# IDCI_WifiNode_CPU1.net
KiCad netlist of a schematic drawn in Altium Designer
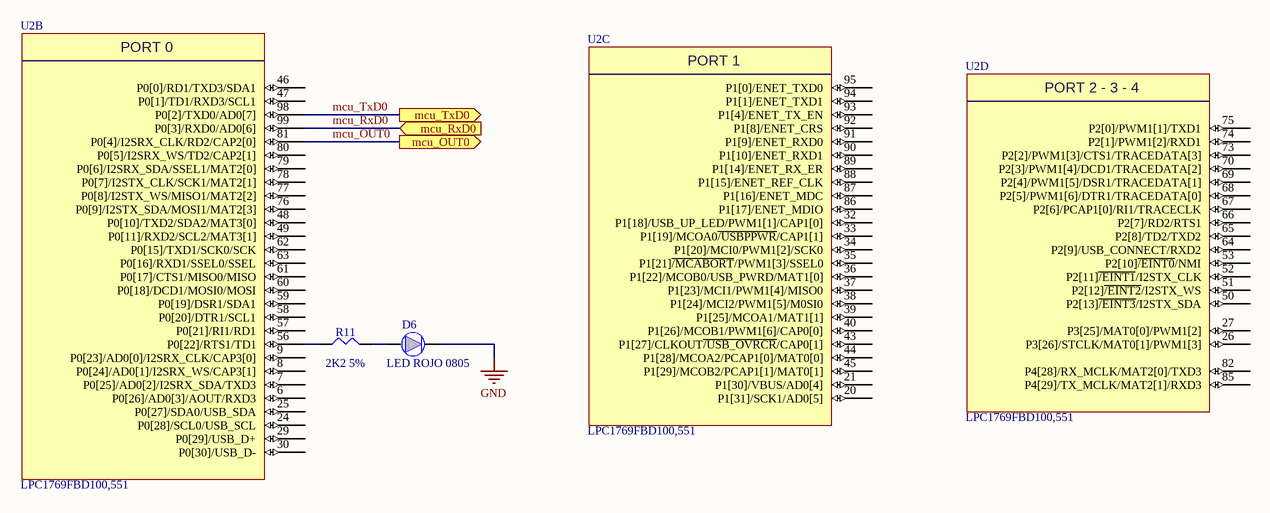
[diagram p0: IDCI_WifiNode_CPU1.SchDoc]

(export (version "E")
  (design (tool "Eeschema 10.0.6"))
  (components
    (comp (ref "D6")
      (value "LED ROJO 0805")
      (footprint "LED_0805")
      (libsource (lib "IDCI_WifiNode_2_R00") (part "LED_DIODE"))
    )
    (comp (ref "R11")
      (value "2K2 5%")
      (footprint "R_0805")
      (libsource (lib "IDCI_WifiNode_2_R00") (part "Resistor"))
    )
    (comp (ref "U2")
      (value "LPC1769FBD100,551")
      (footprint "LQFP_100")
      (description "Mcu Cortex M3 LQFP100")
      (libsource (lib "IDCI_WifiNode_2_R00") (part "LPC1769FBD100_Multipart"))
    )
  )
  (nets
    (net (code "1") (name "/mcu_OUT0") (class "Default")
      (node (ref "U2") (pin "81") (pinfunction "P0[4]/I2SRX_CLK/RD2/CAP2[0]_81") (pintype "bidirectional"))
    )
    (net (code "2") (name "/mcu_RxD0") (class "Default")
      (node (ref "U2") (pin "99") (pinfunction "P0[3]/RXD0/AD0[6]_99") (pintype "bidirectional"))
    )
    (net (code "3") (name "/mcu_TxD0") (class "Default")
      (node (ref "U2") (pin "98") (pinfunction "P0[2]/TXD0/AD0[7]_98") (pintype "bidirectional"))
    )
    (net (code "4") (name "GND") (class "Default")
      (node (ref "D6") (pin "2") (pinfunction "2_2") (pintype "passive"))
    )
    (net (code "5") (name "Net-(D6-Pad1)") (class "Default")
      (node (ref "D6") (pin "1") (pinfunction "1_1") (pintype "passive"))
      (node (ref "R11") (pin "2") (pinfunction "2_2") (pintype "passive"))
    )
    (net (code "6") (name "Net-(U2B-P0[22]{slash}RTS1{slash}TD1)") (class "Default")
      (node (ref "R11") (pin "1") (pinfunction "1_1") (pintype "passive"))
      (node (ref "U2") (pin "56") (pinfunction "P0[22]/RTS1/TD1_56") (pintype "bidirectional"))
    )
    (net (code "7") (name "unconnected-(U2B-P0[0]{slash}RD1{slash}TXD3{slash}SDA1-Pad46)") (class "Default")
      (node (ref "U2") (pin "46") (pinfunction "P0[0]/RD1/TXD3/SDA1_46") (pintype "bidirectional"))
    )
    (net (code "8") (name "unconnected-(U2B-P0[1]{slash}TD1{slash}RXD3{slash}SCL1-Pad47)") (class "Default")
      (node (ref "U2") (pin "47") (pinfunction "P0[1]/TD1/RXD3/SCL1_47") (pintype "bidirectional"))
    )
    (net (code "9") (name "unconnected-(U2B-P0[5]{slash}I2SRX_WS{slash}TD2{slash}CAP2[1]-Pad80)") (class "Default")
      (node (ref "U2") (pin "80") (pinfunction "P0[5]/I2SRX_WS/TD2/CAP2[1]_80") (pintype "bidirectional"))
    )
    (net (code "10") (name "unconnected-(U2B-P0[6]{slash}I2SRX_SDA{slash}SSEL1{slash}MAT2[0]-Pad79)") (class "Default")
      (node (ref "U2") (pin "79") (pinfunction "P0[6]/I2SRX_SDA/SSEL1/MAT2[0]_79") (pintype "bidirectional"))
    )
    (net (code "11") (name "unconnected-(U2B-P0[7]{slash}I2STX_CLK{slash}SCK1{slash}MAT2[1]-Pad78)") (class "Default")
      (node (ref "U2") (pin "78") (pinfunction "P0[7]/I2STX_CLK/SCK1/MAT2[1]_78") (pintype "bidirectional"))
    )
    (net (code "12") (name "unconnected-(U2B-P0[8]{slash}I2STX_WS{slash}MISO1{slash}MAT2[2]-Pad77)") (class "Default")
      (node (ref "U2") (pin "77") (pinfunction "P0[8]/I2STX_WS/MISO1/MAT2[2]_77") (pintype "bidirectional"))
    )
    (net (code "13") (name "unconnected-(U2B-P0[9]{slash}I2STX_SDA{slash}MOSI1{slash}MAT2[3]-Pad76)") (class "Default")
      (node (ref "U2") (pin "76") (pinfunction "P0[9]/I2STX_SDA/MOSI1/MAT2[3]_76") (pintype "bidirectional"))
    )
    (net (code "14") (name "unconnected-(U2B-P0[10]{slash}TXD2{slash}SDA2{slash}MAT3[0]-Pad48)") (class "Default")
      (node (ref "U2") (pin "48") (pinfunction "P0[10]/TXD2/SDA2/MAT3[0]_48") (pintype "bidirectional"))
    )
    (net (code "15") (name "unconnected-(U2B-P0[11]{slash}RXD2{slash}SCL2{slash}MAT3[1]-Pad49)") (class "Default")
      (node (ref "U2") (pin "49") (pinfunction "P0[11]/RXD2/SCL2/MAT3[1]_49") (pintype "bidirectional"))
    )
    (net (code "16") (name "unconnected-(U2B-P0[15]{slash}TXD1{slash}SCK0{slash}SCK-Pad62)") (class "Default")
      (node (ref "U2") (pin "62") (pinfunction "P0[15]/TXD1/SCK0/SCK_62") (pintype "bidirectional"))
    )
    (net (code "17") (name "unconnected-(U2B-P0[16]{slash}RXD1{slash}SSEL0{slash}SSEL-Pad63)") (class "Default")
      (node (ref "U2") (pin "63") (pinfunction "P0[16]/RXD1/SSEL0/SSEL_63") (pintype "bidirectional"))
    )
    (net (code "18") (name "unconnected-(U2B-P0[17]{slash}CTS1{slash}MISO0{slash}MISO-Pad61)") (class "Default")
      (node (ref "U2") (pin "61") (pinfunction "P0[17]/CTS1/MISO0/MISO_61") (pintype "bidirectional"))
    )
    (net (code "19") (name "unconnected-(U2B-P0[18]{slash}DCD1{slash}MOSI0{slash}MOSI-Pad60)") (class "Default")
      (node (ref "U2") (pin "60") (pinfunction "P0[18]/DCD1/MOSI0/MOSI_60") (pintype "bidirectional"))
    )
    (net (code "20") (name "unconnected-(U2B-P0[19]{slash}DSR1{slash}SDA1-Pad59)") (class "Default")
      (node (ref "U2") (pin "59") (pinfunction "P0[19]/DSR1/SDA1_59") (pintype "bidirectional"))
    )
    (net (code "21") (name "unconnected-(U2B-P0[20]{slash}DTR1{slash}SCL1-Pad58)") (class "Default")
      (node (ref "U2") (pin "58") (pinfunction "P0[20]/DTR1/SCL1_58") (pintype "bidirectional"))
    )
    (net (code "22") (name "unconnected-(U2B-P0[21]{slash}RI1{slash}RD1-Pad57)") (class "Default")
      (node (ref "U2") (pin "57") (pinfunction "P0[21]/RI1/RD1_57") (pintype "bidirectional"))
    )
    (net (code "23") (name "unconnected-(U2B-P0[23]{slash}AD0[0]{slash}I2SRX_CLK{slash}CAP3[0]-Pad9)") (class "Default")
      (node (ref "U2") (pin "9") (pinfunction "P0[23]/AD0[0]/I2SRX_CLK/CAP3[0]_9") (pintype "bidirectional"))
    )
    (net (code "24") (name "unconnected-(U2B-P0[24]{slash}AD0[1]{slash}I2SRX_WS{slash}CAP3[1]-Pad8)") (class "Default")
      (node (ref "U2") (pin "8") (pinfunction "P0[24]/AD0[1]/I2SRX_WS/CAP3[1]_8") (pintype "bidirectional"))
    )
    (net (code "25") (name "unconnected-(U2B-P0[25]{slash}AD0[2]{slash}I2SRX_SDA{slash}TXD3-Pad7)") (class "Default")
      (node (ref "U2") (pin "7") (pinfunction "P0[25]/AD0[2]/I2SRX_SDA/TXD3_7") (pintype "bidirectional"))
    )
    (net (code "26") (name "unconnected-(U2B-P0[26]{slash}AD0[3]{slash}AOUT{slash}RXD3-Pad6)") (class "Default")
      (node (ref "U2") (pin "6") (pinfunction "P0[26]/AD0[3]/AOUT/RXD3_6") (pintype "bidirectional"))
    )
    (net (code "27") (name "unconnected-(U2B-P0[27]{slash}SDA0{slash}USB_SDA-Pad25)") (class "Default")
      (node (ref "U2") (pin "25") (pinfunction "P0[27]/SDA0/USB_SDA_25") (pintype "bidirectional"))
    )
    (net (code "28") (name "unconnected-(U2B-P0[28]{slash}SCL0{slash}USB_SCL-Pad24)") (class "Default")
      (node (ref "U2") (pin "24") (pinfunction "P0[28]/SCL0/USB_SCL_24") (pintype "bidirectional"))
    )
    (net (code "29") (name "unconnected-(U2B-P0[29]{slash}USB_D+-Pad29)") (class "Default")
      (node (ref "U2") (pin "29") (pinfunction "P0[29]/USB_D+_29") (pintype "bidirectional"))
    )
    (net (code "30") (name "unconnected-(U2B-P0[30]{slash}USB_D--Pad30)") (class "Default")
      (node (ref "U2") (pin "30") (pinfunction "P0[30]/USB_D-_30") (pintype "bidirectional"))
    )
    (net (code "31") (name "unconnected-(U2C-P1[0]{slash}ENET_TXD0-Pad95)") (class "Default")
      (node (ref "U2") (pin "95") (pinfunction "P1[0]/ENET_TXD0_95") (pintype "bidirectional"))
    )
    (net (code "32") (name "unconnected-(U2C-P1[1]{slash}ENET_TXD1-Pad94)") (class "Default")
      (node (ref "U2") (pin "94") (pinfunction "P1[1]/ENET_TXD1_94") (pintype "bidirectional"))
    )
    (net (code "33") (name "unconnected-(U2C-P1[4]{slash}ENET_TX_EN-Pad93)") (class "Default")
      (node (ref "U2") (pin "93") (pinfunction "P1[4]/ENET_TX_EN_93") (pintype "bidirectional"))
    )
    (net (code "34") (name "unconnected-(U2C-P1[8]{slash}ENET_CRS-Pad92)") (class "Default")
      (node (ref "U2") (pin "92") (pinfunction "P1[8]/ENET_CRS_92") (pintype "bidirectional"))
    )
    (net (code "35") (name "unconnected-(U2C-P1[9]{slash}ENET_RXD0-Pad91)") (class "Default")
      (node (ref "U2") (pin "91") (pinfunction "P1[9]/ENET_RXD0_91") (pintype "bidirectional"))
    )
    (net (code "36") (name "unconnected-(U2C-P1[10]{slash}ENET_RXD1-Pad90)") (class "Default")
      (node (ref "U2") (pin "90") (pinfunction "P1[10]/ENET_RXD1_90") (pintype "bidirectional"))
    )
    (net (code "37") (name "unconnected-(U2C-P1[14]{slash}ENET_RX_ER-Pad89)") (class "Default")
      (node (ref "U2") (pin "89") (pinfunction "P1[14]/ENET_RX_ER_89") (pintype "bidirectional"))
    )
    (net (code "38") (name "unconnected-(U2C-P1[15]{slash}ENET_REF_CLK-Pad88)") (class "Default")
      (node (ref "U2") (pin "88") (pinfunction "P1[15]/ENET_REF_CLK_88") (pintype "bidirectional"))
    )
    (net (code "39") (name "unconnected-(U2C-P1[16]{slash}ENET_MDC-Pad87)") (class "Default")
      (node (ref "U2") (pin "87") (pinfunction "P1[16]/ENET_MDC_87") (pintype "bidirectional"))
    )
    (net (code "40") (name "unconnected-(U2C-P1[17]{slash}ENET_MDIO-Pad86)") (class "Default")
      (node (ref "U2") (pin "86") (pinfunction "P1[17]/ENET_MDIO_86") (pintype "bidirectional"))
    )
    (net (code "41") (name "unconnected-(U2C-P1[18]{slash}USB_UP_LED{slash}PWM1[1]{slash}CAP1[0]-Pad32)") (class "Default")
      (node (ref "U2") (pin "32") (pinfunction "P1[18]/USB_UP_LED/PWM1[1]/CAP1[0]_32") (pintype "bidirectional"))
    )
    (net (code "42") (name "unconnected-(U2C-P1[19]{slash}MCOA0~{{slash}USBPPWR}{slash}CAP1[1]-Pad33)") (class "Default")
      (node (ref "U2") (pin "33") (pinfunction "P1[19]/MCOA0~{/USBPPWR}/CAP1[1]_33") (pintype "bidirectional"))
    )
    (net (code "43") (name "unconnected-(U2C-P1[20]{slash}MCI0{slash}PWM1[2]{slash}SCK0-Pad34)") (class "Default")
      (node (ref "U2") (pin "34") (pinfunction "P1[20]/MCI0/PWM1[2]/SCK0_34") (pintype "bidirectional"))
    )
    (net (code "44") (name "unconnected-(U2C-P1[21]~{{slash}MCABORT}{slash}PWM1[3]{slash}SSEL0-Pad35)") (class "Default")
      (node (ref "U2") (pin "35") (pinfunction "P1[21]~{/MCABORT}/PWM1[3]/SSEL0_35") (pintype "bidirectional"))
    )
    (net (code "45") (name "unconnected-(U2C-P1[22]{slash}MCOB0{slash}USB_PWRD{slash}MAT1[0]-Pad36)") (class "Default")
      (node (ref "U2") (pin "36") (pinfunction "P1[22]/MCOB0/USB_PWRD/MAT1[0]_36") (pintype "bidirectional"))
    )
    (net (code "46") (name "unconnected-(U2C-P1[23]{slash}MCI1{slash}PWM1[4]{slash}MISO0-Pad37)") (class "Default")
      (node (ref "U2") (pin "37") (pinfunction "P1[23]/MCI1/PWM1[4]/MISO0_37") (pintype "bidirectional"))
    )
    (net (code "47") (name "unconnected-(U2C-P1[24]{slash}MCI2{slash}PWM1[5]{slash}M0SI0-Pad38)") (class "Default")
      (node (ref "U2") (pin "38") (pinfunction "P1[24]/MCI2/PWM1[5]/M0SI0_38") (pintype "bidirectional"))
    )
    (net (code "48") (name "unconnected-(U2C-P1[25]{slash}MCOA1{slash}MAT1[1]-Pad39)") (class "Default")
      (node (ref "U2") (pin "39") (pinfunction "P1[25]/MCOA1/MAT1[1]_39") (pintype "bidirectional"))
    )
    (net (code "49") (name "unconnected-(U2C-P1[26]{slash}MCOB1{slash}PWM1[6]{slash}CAP0[0]-Pad40)") (class "Default")
      (node (ref "U2") (pin "40") (pinfunction "P1[26]/MCOB1/PWM1[6]/CAP0[0]_40") (pintype "bidirectional"))
    )
    (net (code "50") (name "unconnected-(U2C-P1[27]{slash}CLKOUT~{{slash}USB_OVRCR}{slash}CAP0[1]-Pad43)") (class "Default")
      (node (ref "U2") (pin "43") (pinfunction "P1[27]/CLKOUT~{/USB_OVRCR}/CAP0[1]_43") (pintype "bidirectional"))
    )
    (net (code "51") (name "unconnected-(U2C-P1[28]{slash}MCOA2{slash}PCAP1[0]{slash}MAT0[0]-Pad44)") (class "Default")
      (node (ref "U2") (pin "44") (pinfunction "P1[28]/MCOA2/PCAP1[0]/MAT0[0]_44") (pintype "bidirectional"))
    )
    (net (code "52") (name "unconnected-(U2C-P1[29]{slash}MCOB2{slash}PCAP1[1]{slash}MAT0[1]-Pad45)") (class "Default")
      (node (ref "U2") (pin "45") (pinfunction "P1[29]/MCOB2/PCAP1[1]/MAT0[1]_45") (pintype "bidirectional"))
    )
    (net (code "53") (name "unconnected-(U2C-P1[30]{slash}VBUS{slash}AD0[4]-Pad21)") (class "Default")
      (node (ref "U2") (pin "21") (pinfunction "P1[30]/VBUS/AD0[4]_21") (pintype "bidirectional"))
    )
    (net (code "54") (name "unconnected-(U2C-P1[31]{slash}SCK1{slash}AD0[5]-Pad20)") (class "Default")
      (node (ref "U2") (pin "20") (pinfunction "P1[31]/SCK1/AD0[5]_20") (pintype "bidirectional"))
    )
    (net (code "55") (name "unconnected-(U2D-P2[0]{slash}PWM1[1]{slash}TXD1-Pad75)") (class "Default")
      (node (ref "U2") (pin "75") (pinfunction "P2[0]/PWM1[1]/TXD1_75") (pintype "bidirectional"))
    )
    (net (code "56") (name "unconnected-(U2D-P2[1]{slash}PWM1[2]{slash}RXD1-Pad74)") (class "Default")
      (node (ref "U2") (pin "74") (pinfunction "P2[1]/PWM1[2]/RXD1_74") (pintype "bidirectional"))
    )
    (net (code "57") (name "unconnected-(U2D-P2[2]{slash}PWM1[3]{slash}CTS1{slash}TRACEDATA[3]-Pad73)") (class "Default")
      (node (ref "U2") (pin "73") (pinfunction "P2[2]/PWM1[3]/CTS1/TRACEDATA[3]_73") (pintype "bidirectional"))
    )
    (net (code "58") (name "unconnected-(U2D-P2[3]{slash}PWM1[4]{slash}DCD1{slash}TRACEDATA[2]-Pad70)") (class "Default")
      (node (ref "U2") (pin "70") (pinfunction "P2[3]/PWM1[4]/DCD1/TRACEDATA[2]_70") (pintype "bidirectional"))
    )
    (net (code "59") (name "unconnected-(U2D-P2[4]{slash}PWM1[5]{slash}DSR1{slash}TRACEDATA[1]-Pad69)") (class "Default")
      (node (ref "U2") (pin "69") (pinfunction "P2[4]/PWM1[5]/DSR1/TRACEDATA[1]_69") (pintype "bidirectional"))
    )
    (net (code "60") (name "unconnected-(U2D-P2[5]{slash}PWM1[6]{slash}DTR1{slash}TRACEDATA[0]-Pad68)") (class "Default")
      (node (ref "U2") (pin "68") (pinfunction "P2[5]/PWM1[6]/DTR1/TRACEDATA[0]_68") (pintype "bidirectional"))
    )
    (net (code "61") (name "unconnected-(U2D-P2[6]{slash}PCAP1[0]{slash}RI1{slash}TRACECLK-Pad67)") (class "Default")
      (node (ref "U2") (pin "67") (pinfunction "P2[6]/PCAP1[0]/RI1/TRACECLK_67") (pintype "bidirectional"))
    )
    (net (code "62") (name "unconnected-(U2D-P2[7]{slash}RD2{slash}RTS1-Pad66)") (class "Default")
      (node (ref "U2") (pin "66") (pinfunction "P2[7]/RD2/RTS1_66") (pintype "bidirectional"))
    )
    (net (code "63") (name "unconnected-(U2D-P2[8]{slash}TD2{slash}TXD2-Pad65)") (class "Default")
      (node (ref "U2") (pin "65") (pinfunction "P2[8]/TD2/TXD2_65") (pintype "bidirectional"))
    )
    (net (code "64") (name "unconnected-(U2D-P2[9]{slash}USB_CONNECT{slash}RXD2-Pad64)") (class "Default")
      (node (ref "U2") (pin "64") (pinfunction "P2[9]/USB_CONNECT/RXD2_64") (pintype "bidirectional"))
    )
    (net (code "65") (name "unconnected-(U2D-P2[10]~{{slash}EINT0}{slash}NMI-Pad53)") (class "Default")
      (node (ref "U2") (pin "53") (pinfunction "P2[10]~{/EINT0}/NMI_53") (pintype "bidirectional"))
    )
    (net (code "66") (name "unconnected-(U2D-P2[11]~{{slash}EINT1}{slash}I2STX_CLK-Pad52)") (class "Default")
      (node (ref "U2") (pin "52") (pinfunction "P2[11]~{/EINT1}/I2STX_CLK_52") (pintype "bidirectional"))
    )
    (net (code "67") (name "unconnected-(U2D-P2[12]~{{slash}EINT2}{slash}I2STX_WS-Pad51)") (class "Default")
      (node (ref "U2") (pin "51") (pinfunction "P2[12]~{/EINT2}/I2STX_WS_51") (pintype "bidirectional"))
    )
    (net (code "68") (name "unconnected-(U2D-P2[13]~{{slash}EINT3}{slash}I2STX_SDA-Pad50)") (class "Default")
      (node (ref "U2") (pin "50") (pinfunction "P2[13]~{/EINT3}/I2STX_SDA_50") (pintype "bidirectional"))
    )
    (net (code "69") (name "unconnected-(U2D-P3[25]{slash}MAT0[0]{slash}PWM1[2]-Pad27)") (class "Default")
      (node (ref "U2") (pin "27") (pinfunction "P3[25]/MAT0[0]/PWM1[2]_27") (pintype "bidirectional"))
    )
    (net (code "70") (name "unconnected-(U2D-P3[26]{slash}STCLK{slash}MAT0[1]{slash}PWM1[3]-Pad26)") (class "Default")
      (node (ref "U2") (pin "26") (pinfunction "P3[26]/STCLK/MAT0[1]/PWM1[3]_26") (pintype "bidirectional"))
    )
    (net (code "71") (name "unconnected-(U2D-P4[28]{slash}RX_MCLK{slash}MAT2[0]{slash}TXD3-Pad82)") (class "Default")
      (node (ref "U2") (pin "82") (pinfunction "P4[28]/RX_MCLK/MAT2[0]/TXD3_82") (pintype "bidirectional"))
    )
    (net (code "72") (name "unconnected-(U2D-P4[29]{slash}TX_MCLK{slash}MAT2[1]{slash}RXD3-Pad85)") (class "Default")
      (node (ref "U2") (pin "85") (pinfunction "P4[29]/TX_MCLK/MAT2[1]/RXD3_85") (pintype "bidirectional"))
    )
  )
)
